# Atmega162_prj_board.net
KiCad netlist of a schematic drawn in EAGLE
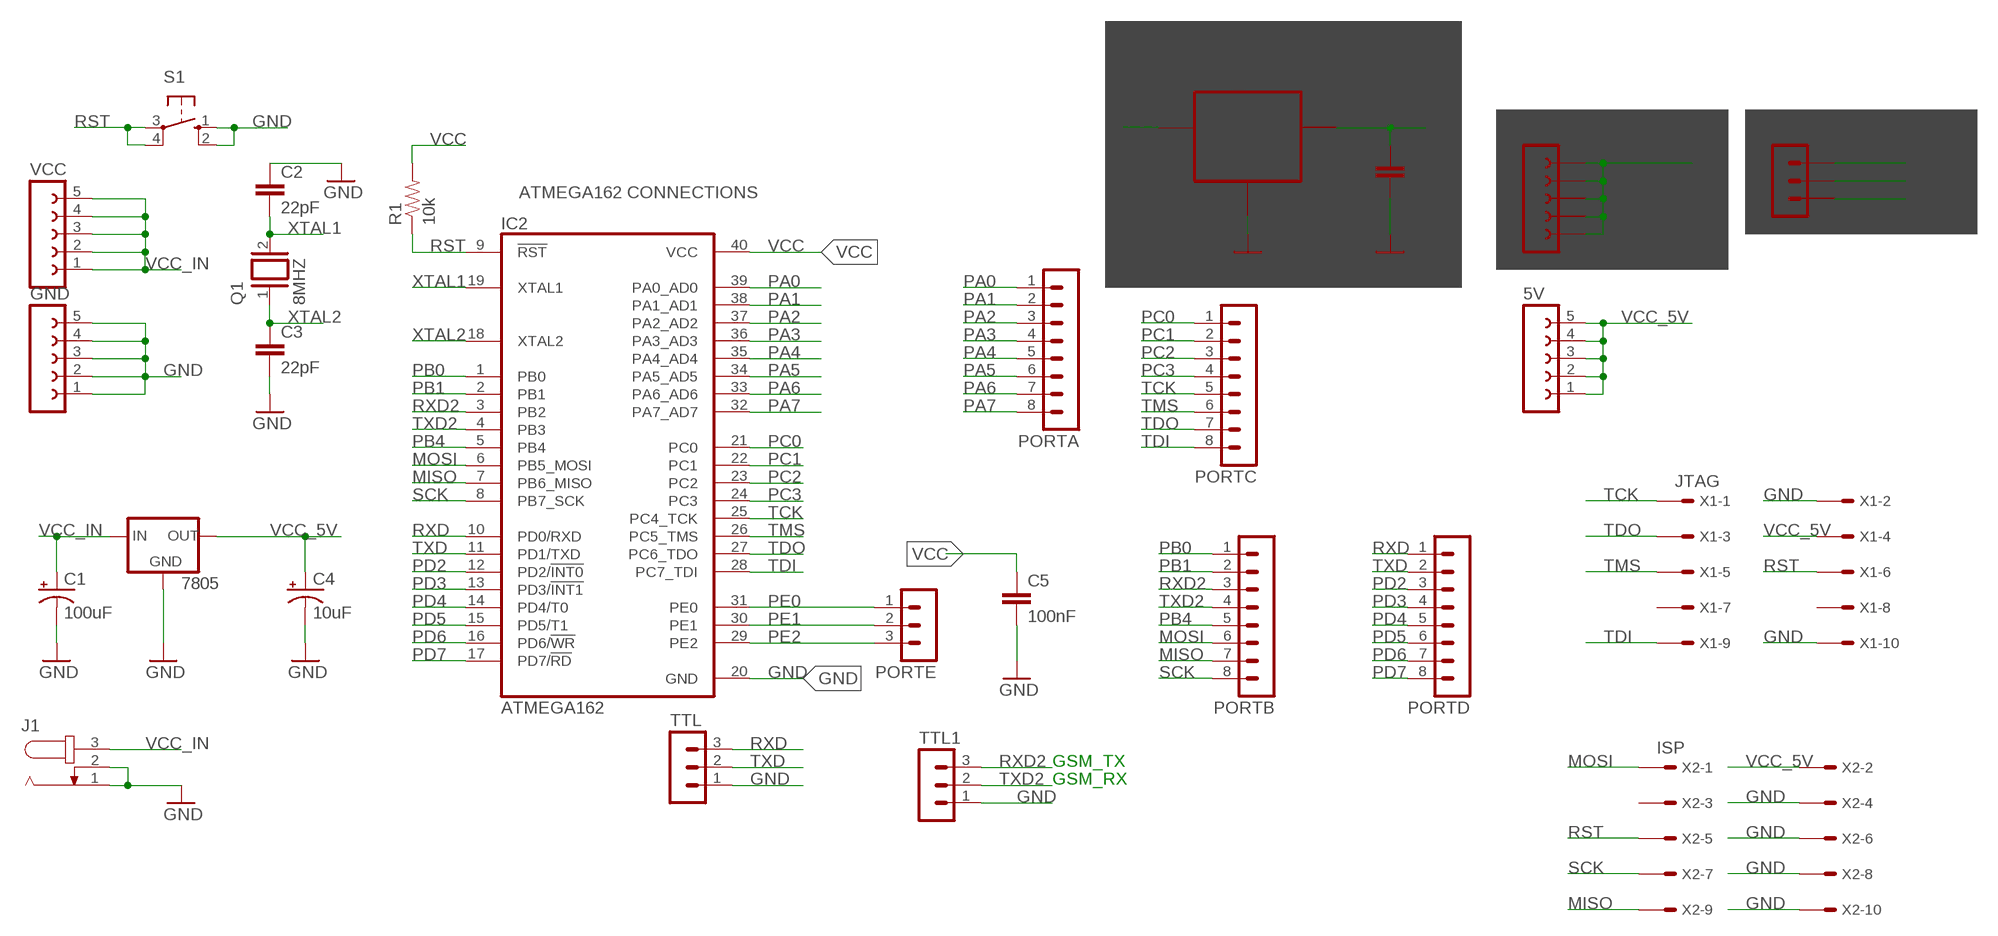
[diagram p0: schematic, sheet 1]

(export (version "E")
  (design (tool "Eeschema 10.0.6"))
  (components
    (comp (ref "3.3V")
      (value "FE05-1")
      (footprint "eagle-import:FE05-1")
      (libsource (lib "eagle-import") (part "FE05-1"))
    )
    (comp (ref "5V")
      (value "FE05-1")
      (footprint "eagle-import:FE05-1")
      (libsource (lib "eagle-import") (part "FE05-1"))
    )
    (comp (ref "7805")
      (value "78XXS")
      (footprint "eagle-import:78XXS")
      (libsource (lib "eagle-import") (part "78XXS"))
    )
    (comp (ref "C1")
      (value "100uF")
      (footprint "eagle-import:CPOL-RADIAL-100UF-25V")
      (libsource (lib "eagle-import") (part "CAP_POLPTH1"))
    )
    (comp (ref "C2")
      (value "22pF")
      (footprint "eagle-import:CAP-PTH-SMALLEZ")
      (libsource (lib "eagle-import") (part "CAPEZ"))
    )
    (comp (ref "C3")
      (value "22pF")
      (footprint "eagle-import:CAP-PTH-SMALLEZ")
      (libsource (lib "eagle-import") (part "CAPEZ"))
    )
    (comp (ref "C4")
      (value "10uF")
      (footprint "eagle-import:CPOL-RADIAL-10UF-25V")
      (libsource (lib "eagle-import") (part "CAP_POLPTH2"))
    )
    (comp (ref "C5")
      (value "100nF")
      (footprint "eagle-import:0805")
      (libsource (lib "eagle-import") (part "CAP0805"))
    )
    (comp (ref "C8")
      (value "10uF")
      (footprint "eagle-import:0805")
      (libsource (lib "eagle-import") (part "1.0UF-25V-+80/-20(0805)"))
    )
    (comp (ref "GND")
      (value "FE05-1")
      (footprint "eagle-import:FE05-1")
      (libsource (lib "eagle-import") (part "FE05-1"))
    )
    (comp (ref "IC2")
      (value "ATMEGA162")
      (footprint "eagle-import:DIL40")
      (fields (field (name "MPN") "AT89S51-24PU"))
      (libsource (lib "eagle-import") (part "AT89S51-P24"))
    )
    (comp (ref "J1")
      (value "JACK-PLUG0")
      (footprint "eagle-import:SPC4077")
      (libsource (lib "eagle-import") (part "JACK-PLUG0"))
    )
    (comp (ref "PORTA")
      (value "MA08-1")
      (footprint "eagle-import:MA08-1")
      (libsource (lib "eagle-import") (part "MA08-1"))
    )
    (comp (ref "PORTB")
      (value "MA08-1")
      (footprint "eagle-import:MA08-1")
      (libsource (lib "eagle-import") (part "MA08-1"))
    )
    (comp (ref "PORTC")
      (value "MA08-1")
      (footprint "eagle-import:MA08-1")
      (libsource (lib "eagle-import") (part "MA08-1"))
    )
    (comp (ref "PORTD")
      (value "MA08-1")
      (footprint "eagle-import:MA08-1")
      (libsource (lib "eagle-import") (part "MA08-1"))
    )
    (comp (ref "PORTE")
      (value "MA03-1")
      (footprint "eagle-import:MA03-1")
      (libsource (lib "eagle-import") (part "MA03-1"))
    )
    (comp (ref "Q1")
      (value "8MHZ")
      (footprint "eagle-import:QS")
      (libsource (lib "eagle-import") (part "XTAL/S"))
    )
    (comp (ref "R1")
      (value "10k")
      (footprint "eagle-import:AXIAL-0.3")
      (libsource (lib "eagle-import") (part "10KOHM-1/4W-1%(PTH)HORIZ"))
    )
    (comp (ref "REG_3.3V")
      (value "REG1117")
      (footprint "eagle-import:SOT223")
      (libsource (lib "eagle-import") (part "REG1117"))
    )
    (comp (ref "S1")
      (value "10-XX")
      (footprint "eagle-import:B3F-10XX")
      (fields (field (name "MPN") "B3F-1000"))
      (libsource (lib "eagle-import") (part "10-XX"))
    )
    (comp (ref "TTL")
      (value "MA03-1")
      (footprint "eagle-import:MA03-1")
      (libsource (lib "eagle-import") (part "MA03-1"))
    )
    (comp (ref "TTL1")
      (value "MA03-1")
      (footprint "eagle-import:MA03-1")
      (libsource (lib "eagle-import") (part "MA03-1"))
    )
    (comp (ref "VCC")
      (value "FE05-1")
      (footprint "eagle-import:FE05-1")
      (libsource (lib "eagle-import") (part "FE05-1"))
    )
    (comp (ref "VCC_SEL")
      (value "MA03-1")
      (footprint "eagle-import:MA03-1")
      (libsource (lib "eagle-import") (part "MA03-1"))
    )
    (comp (ref "X1")
      (value "JTAG")
      (footprint "eagle-import:057-010-1")
      (libsource (lib "eagle-import") (part "057-010-1"))
    )
    (comp (ref "X2")
      (value "ISP")
      (footprint "eagle-import:057-010-1")
      (libsource (lib "eagle-import") (part "057-010-1"))
    )
  )
  (nets
    (net (code "1") (name "/MISO") (class "Default")
      (node (ref "IC2") (pin "7") (pinfunction "PB6_MISO_7") (pintype "bidirectional"))
      (node (ref "PORTB") (pin "7") (pinfunction "7_7") (pintype "passive"))
      (node (ref "X2") (pin "9") (pinfunction "S_9") (pintype "passive"))
    )
    (net (code "2") (name "/MOSI") (class "Default")
      (node (ref "IC2") (pin "6") (pinfunction "PB5_MOSI_6") (pintype "bidirectional"))
      (node (ref "PORTB") (pin "6") (pinfunction "6_6") (pintype "passive"))
      (node (ref "X2") (pin "1") (pinfunction "S_1") (pintype "passive"))
    )
    (net (code "3") (name "/PA0") (class "Default")
      (node (ref "IC2") (pin "39") (pinfunction "PA0_AD0_39") (pintype "bidirectional"))
      (node (ref "PORTA") (pin "1") (pinfunction "1_1") (pintype "passive"))
    )
    (net (code "4") (name "/PA1") (class "Default")
      (node (ref "IC2") (pin "38") (pinfunction "PA1_AD1_38") (pintype "bidirectional"))
      (node (ref "PORTA") (pin "2") (pinfunction "2_2") (pintype "passive"))
    )
    (net (code "5") (name "/PA2") (class "Default")
      (node (ref "IC2") (pin "37") (pinfunction "PA2_AD2_37") (pintype "bidirectional"))
      (node (ref "PORTA") (pin "3") (pinfunction "3_3") (pintype "passive"))
    )
    (net (code "6") (name "/PA3") (class "Default")
      (node (ref "IC2") (pin "36") (pinfunction "PA3_AD3_36") (pintype "bidirectional"))
      (node (ref "PORTA") (pin "4") (pinfunction "4_4") (pintype "passive"))
    )
    (net (code "7") (name "/PA4") (class "Default")
      (node (ref "IC2") (pin "35") (pinfunction "PA4_AD4_35") (pintype "bidirectional"))
      (node (ref "PORTA") (pin "5") (pinfunction "5_5") (pintype "passive"))
    )
    (net (code "8") (name "/PA5") (class "Default")
      (node (ref "IC2") (pin "34") (pinfunction "PA5_AD5_34") (pintype "bidirectional"))
      (node (ref "PORTA") (pin "6") (pinfunction "6_6") (pintype "passive"))
    )
    (net (code "9") (name "/PA6") (class "Default")
      (node (ref "IC2") (pin "33") (pinfunction "PA6_AD6_33") (pintype "bidirectional"))
      (node (ref "PORTA") (pin "7") (pinfunction "7_7") (pintype "passive"))
    )
    (net (code "10") (name "/PA7") (class "Default")
      (node (ref "IC2") (pin "32") (pinfunction "PA7_AD7_32") (pintype "bidirectional"))
      (node (ref "PORTA") (pin "8") (pinfunction "8_8") (pintype "passive"))
    )
    (net (code "11") (name "/PB0") (class "Default")
      (node (ref "IC2") (pin "1") (pinfunction "PB0_1") (pintype "bidirectional"))
      (node (ref "PORTB") (pin "1") (pinfunction "1_1") (pintype "passive"))
    )
    (net (code "12") (name "/PB1") (class "Default")
      (node (ref "IC2") (pin "2") (pinfunction "PB1_2") (pintype "bidirectional"))
      (node (ref "PORTB") (pin "2") (pinfunction "2_2") (pintype "passive"))
    )
    (net (code "13") (name "/PB4") (class "Default")
      (node (ref "IC2") (pin "5") (pinfunction "PB4_5") (pintype "bidirectional"))
      (node (ref "PORTB") (pin "5") (pinfunction "5_5") (pintype "passive"))
    )
    (net (code "14") (name "/PC0") (class "Default")
      (node (ref "IC2") (pin "21") (pinfunction "PC0_21") (pintype "bidirectional"))
      (node (ref "PORTC") (pin "1") (pinfunction "1_1") (pintype "passive"))
    )
    (net (code "15") (name "/PC1") (class "Default")
      (node (ref "IC2") (pin "22") (pinfunction "PC1_22") (pintype "bidirectional"))
      (node (ref "PORTC") (pin "2") (pinfunction "2_2") (pintype "passive"))
    )
    (net (code "16") (name "/PC2") (class "Default")
      (node (ref "IC2") (pin "23") (pinfunction "PC2_23") (pintype "bidirectional"))
      (node (ref "PORTC") (pin "3") (pinfunction "3_3") (pintype "passive"))
    )
    (net (code "17") (name "/PC3") (class "Default")
      (node (ref "IC2") (pin "24") (pinfunction "PC3_24") (pintype "bidirectional"))
      (node (ref "PORTC") (pin "4") (pinfunction "4_4") (pintype "passive"))
    )
    (net (code "18") (name "/PD2") (class "Default")
      (node (ref "IC2") (pin "12") (pinfunction "PD2/~{INT0}_12") (pintype "bidirectional"))
      (node (ref "PORTD") (pin "3") (pinfunction "3_3") (pintype "passive"))
    )
    (net (code "19") (name "/PD3") (class "Default")
      (node (ref "IC2") (pin "13") (pinfunction "PD3/~{INT1}_13") (pintype "bidirectional"))
      (node (ref "PORTD") (pin "4") (pinfunction "4_4") (pintype "passive"))
    )
    (net (code "20") (name "/PD4") (class "Default")
      (node (ref "IC2") (pin "14") (pinfunction "PD4/T0_14") (pintype "bidirectional"))
      (node (ref "PORTD") (pin "5") (pinfunction "5_5") (pintype "passive"))
    )
    (net (code "21") (name "/PD5") (class "Default")
      (node (ref "IC2") (pin "15") (pinfunction "PD5/T1_15") (pintype "bidirectional"))
      (node (ref "PORTD") (pin "6") (pinfunction "6_6") (pintype "passive"))
    )
    (net (code "22") (name "/PD6") (class "Default")
      (node (ref "IC2") (pin "16") (pinfunction "PD6/~{WR}_16") (pintype "bidirectional"))
      (node (ref "PORTD") (pin "7") (pinfunction "7_7") (pintype "passive"))
    )
    (net (code "23") (name "/PD7") (class "Default")
      (node (ref "IC2") (pin "17") (pinfunction "PD7/~{RD}_17") (pintype "bidirectional"))
      (node (ref "PORTD") (pin "8") (pinfunction "8_8") (pintype "passive"))
    )
    (net (code "24") (name "/PE0") (class "Default")
      (node (ref "IC2") (pin "31") (pinfunction "PE0_31") (pintype "input"))
      (node (ref "PORTE") (pin "1") (pinfunction "1_1") (pintype "passive"))
    )
    (net (code "25") (name "/PE1") (class "Default")
      (node (ref "IC2") (pin "30") (pinfunction "PE1_30") (pintype "output"))
      (node (ref "PORTE") (pin "2") (pinfunction "2_2") (pintype "passive"))
    )
    (net (code "26") (name "/PE2") (class "Default")
      (node (ref "IC2") (pin "29") (pinfunction "PE2_29") (pintype "output"))
      (node (ref "PORTE") (pin "3") (pinfunction "3_3") (pintype "passive"))
    )
    (net (code "27") (name "/RST") (class "Default")
      (node (ref "IC2") (pin "9") (pinfunction "~{RST}_9") (pintype "input"))
      (node (ref "R1") (pin "P$1") (pinfunction "1_P$1") (pintype "passive"))
      (node (ref "S1") (pin "3") (pinfunction "P_3") (pintype "passive"))
      (node (ref "S1") (pin "4") (pinfunction "P1_4") (pintype "passive"))
      (node (ref "X1") (pin "6") (pinfunction "S_6") (pintype "passive"))
      (node (ref "X2") (pin "5") (pinfunction "S_5") (pintype "passive"))
    )
    (net (code "28") (name "/RXD") (class "Default")
      (node (ref "IC2") (pin "10") (pinfunction "PD0/RXD_10") (pintype "bidirectional"))
      (node (ref "PORTD") (pin "1") (pinfunction "1_1") (pintype "passive"))
      (node (ref "TTL") (pin "3") (pinfunction "3_3") (pintype "passive"))
    )
    (net (code "29") (name "/RXD2") (class "Default")
      (node (ref "IC2") (pin "3") (pinfunction "PB2_3") (pintype "bidirectional"))
      (node (ref "PORTB") (pin "3") (pinfunction "3_3") (pintype "passive"))
      (node (ref "TTL1") (pin "3") (pinfunction "3_3") (pintype "passive"))
    )
    (net (code "30") (name "/SCK") (class "Default")
      (node (ref "IC2") (pin "8") (pinfunction "PB7_SCK_8") (pintype "bidirectional"))
      (node (ref "PORTB") (pin "8") (pinfunction "8_8") (pintype "passive"))
      (node (ref "X2") (pin "7") (pinfunction "S_7") (pintype "passive"))
    )
    (net (code "31") (name "/TCK") (class "Default")
      (node (ref "IC2") (pin "25") (pinfunction "PC4_TCK_25") (pintype "bidirectional"))
      (node (ref "PORTC") (pin "5") (pinfunction "5_5") (pintype "passive"))
      (node (ref "X1") (pin "1") (pinfunction "S_1") (pintype "passive"))
    )
    (net (code "32") (name "/TDI") (class "Default")
      (node (ref "IC2") (pin "28") (pinfunction "PC7_TDI_28") (pintype "bidirectional"))
      (node (ref "PORTC") (pin "8") (pinfunction "8_8") (pintype "passive"))
      (node (ref "X1") (pin "9") (pinfunction "S_9") (pintype "passive"))
    )
    (net (code "33") (name "/TDO") (class "Default")
      (node (ref "IC2") (pin "27") (pinfunction "PC6_TDO_27") (pintype "bidirectional"))
      (node (ref "PORTC") (pin "7") (pinfunction "7_7") (pintype "passive"))
      (node (ref "X1") (pin "3") (pinfunction "S_3") (pintype "passive"))
    )
    (net (code "34") (name "/TMS") (class "Default")
      (node (ref "IC2") (pin "26") (pinfunction "PC5_TMS_26") (pintype "bidirectional"))
      (node (ref "PORTC") (pin "6") (pinfunction "6_6") (pintype "passive"))
      (node (ref "X1") (pin "5") (pinfunction "S_5") (pintype "passive"))
    )
    (net (code "35") (name "/TXD") (class "Default")
      (node (ref "IC2") (pin "11") (pinfunction "PD1/TXD_11") (pintype "bidirectional"))
      (node (ref "PORTD") (pin "2") (pinfunction "2_2") (pintype "passive"))
      (node (ref "TTL") (pin "2") (pinfunction "2_2") (pintype "passive"))
    )
    (net (code "36") (name "/TXD2") (class "Default")
      (node (ref "IC2") (pin "4") (pinfunction "PB3_4") (pintype "bidirectional"))
      (node (ref "PORTB") (pin "4") (pinfunction "4_4") (pintype "passive"))
      (node (ref "TTL1") (pin "2") (pinfunction "2_2") (pintype "passive"))
    )
    (net (code "37") (name "/VCC_3.3V") (class "Default")
      (node (ref "3.3V") (pin "1") (pinfunction "1_1") (pintype "passive"))
      (node (ref "3.3V") (pin "2") (pinfunction "2_2") (pintype "passive"))
      (node (ref "3.3V") (pin "3") (pinfunction "3_3") (pintype "passive"))
      (node (ref "3.3V") (pin "4") (pinfunction "4_4") (pintype "passive"))
      (node (ref "3.3V") (pin "5") (pinfunction "5_5") (pintype "passive"))
      (node (ref "C8") (pin "1") (pinfunction "1_1") (pintype "passive"))
      (node (ref "REG_3.3V") (pin "2") (pinfunction "VOUT_2") (pintype "output"))
      (node (ref "VCC_SEL") (pin "1") (pinfunction "1_1") (pintype "passive"))
    )
    (net (code "38") (name "/VCC_5V") (class "Default")
      (node (ref "5V") (pin "1") (pinfunction "1_1") (pintype "passive"))
      (node (ref "5V") (pin "2") (pinfunction "2_2") (pintype "passive"))
      (node (ref "5V") (pin "3") (pinfunction "3_3") (pintype "passive"))
      (node (ref "5V") (pin "4") (pinfunction "4_4") (pintype "passive"))
      (node (ref "5V") (pin "5") (pinfunction "5_5") (pintype "passive"))
      (node (ref "7805") (pin "OUT") (pinfunction "OUT_OUT") (pintype "passive"))
      (node (ref "C4") (pin "1") (pinfunction "+_1") (pintype "passive"))
      (node (ref "REG_3.3V") (pin "3") (pinfunction "VIN_3") (pintype "input"))
      (node (ref "VCC_SEL") (pin "3") (pinfunction "3_3") (pintype "passive"))
      (node (ref "X1") (pin "4") (pinfunction "S_4") (pintype "passive"))
      (node (ref "X2") (pin "2") (pinfunction "S_2") (pintype "passive"))
    )
    (net (code "39") (name "/VCC_IN") (class "Default")
      (node (ref "7805") (pin "IN") (pinfunction "IN_IN") (pintype "input"))
      (node (ref "C1") (pin "1") (pinfunction "+_1") (pintype "passive"))
      (node (ref "J1") (pin "3") (pinfunction "3_3") (pintype "passive"))
      (node (ref "VCC") (pin "1") (pinfunction "1_1") (pintype "passive"))
      (node (ref "VCC") (pin "2") (pinfunction "2_2") (pintype "passive"))
      (node (ref "VCC") (pin "3") (pinfunction "3_3") (pintype "passive"))
      (node (ref "VCC") (pin "4") (pinfunction "4_4") (pintype "passive"))
      (node (ref "VCC") (pin "5") (pinfunction "5_5") (pintype "passive"))
    )
    (net (code "40") (name "/XTAL1") (class "Default")
      (node (ref "C2") (pin "2") (pinfunction "2_2") (pintype "passive"))
      (node (ref "IC2") (pin "19") (pinfunction "XTAL1_19") (pintype "input"))
      (node (ref "Q1") (pin "2") (pinfunction "2_2") (pintype "passive"))
    )
    (net (code "41") (name "/XTAL2") (class "Default")
      (node (ref "C3") (pin "1") (pinfunction "1_1") (pintype "passive"))
      (node (ref "IC2") (pin "18") (pinfunction "XTAL2_18") (pintype "input"))
      (node (ref "Q1") (pin "1") (pinfunction "1_1") (pintype "passive"))
    )
    (net (code "42") (name "GND") (class "Default")
      (node (ref "7805") (pin "GND") (pinfunction "GND_GND") (pintype "input"))
      (node (ref "C1") (pin "2") (pinfunction "-_2") (pintype "passive"))
      (node (ref "C2") (pin "1") (pinfunction "1_1") (pintype "passive"))
      (node (ref "C3") (pin "2") (pinfunction "2_2") (pintype "passive"))
      (node (ref "C4") (pin "2") (pinfunction "-_2") (pintype "passive"))
      (node (ref "C5") (pin "2") (pinfunction "2_2") (pintype "passive"))
      (node (ref "C8") (pin "2") (pinfunction "2_2") (pintype "passive"))
      (node (ref "GND") (pin "1") (pinfunction "1_1") (pintype "passive"))
      (node (ref "GND") (pin "2") (pinfunction "2_2") (pintype "passive"))
      (node (ref "GND") (pin "3") (pinfunction "3_3") (pintype "passive"))
      (node (ref "GND") (pin "4") (pinfunction "4_4") (pintype "passive"))
      (node (ref "GND") (pin "5") (pinfunction "5_5") (pintype "passive"))
      (node (ref "IC2") (pin "20") (pinfunction "GND_20") (pintype "power_in"))
      (node (ref "J1") (pin "1") (pinfunction "1_1") (pintype "passive"))
      (node (ref "J1") (pin "2") (pinfunction "2_2") (pintype "passive"))
      (node (ref "REG_3.3V") (pin "1") (pinfunction "GND_1") (pintype "power_in"))
      (node (ref "S1") (pin "1") (pinfunction "S_1") (pintype "passive"))
      (node (ref "S1") (pin "2") (pinfunction "S1_2") (pintype "passive"))
      (node (ref "TTL") (pin "1") (pinfunction "1_1") (pintype "passive"))
      (node (ref "TTL1") (pin "1") (pinfunction "1_1") (pintype "passive"))
      (node (ref "X1") (pin "10") (pinfunction "S_10") (pintype "passive"))
      (node (ref "X1") (pin "2") (pinfunction "S_2") (pintype "passive"))
      (node (ref "X2") (pin "10") (pinfunction "S_10") (pintype "passive"))
      (node (ref "X2") (pin "4") (pinfunction "S_4") (pintype "passive"))
      (node (ref "X2") (pin "6") (pinfunction "S_6") (pintype "passive"))
      (node (ref "X2") (pin "8") (pinfunction "S_8") (pintype "passive"))
    )
    (net (code "43") (name "VCC") (class "Default")
      (node (ref "C5") (pin "1") (pinfunction "1_1") (pintype "passive"))
      (node (ref "IC2") (pin "40") (pinfunction "VCC_40") (pintype "power_in"))
      (node (ref "R1") (pin "P$2") (pinfunction "2_P$2") (pintype "passive"))
      (node (ref "VCC_SEL") (pin "2") (pinfunction "2_2") (pintype "passive"))
    )
    (net (code "44") (name "unconnected-(X1H-S-Pad7)") (class "Default")
      (node (ref "X1") (pin "7") (pinfunction "S_7") (pintype "passive"))
    )
    (net (code "45") (name "unconnected-(X1I-S-Pad8)") (class "Default")
      (node (ref "X1") (pin "8") (pinfunction "S_8") (pintype "passive"))
    )
    (net (code "46") (name "unconnected-(X2D-S-Pad3)") (class "Default")
      (node (ref "X2") (pin "3") (pinfunction "S_3") (pintype "passive"))
    )
  )
)
